# SUPPLY.net
KiCad netlist of a schematic drawn in EAGLE
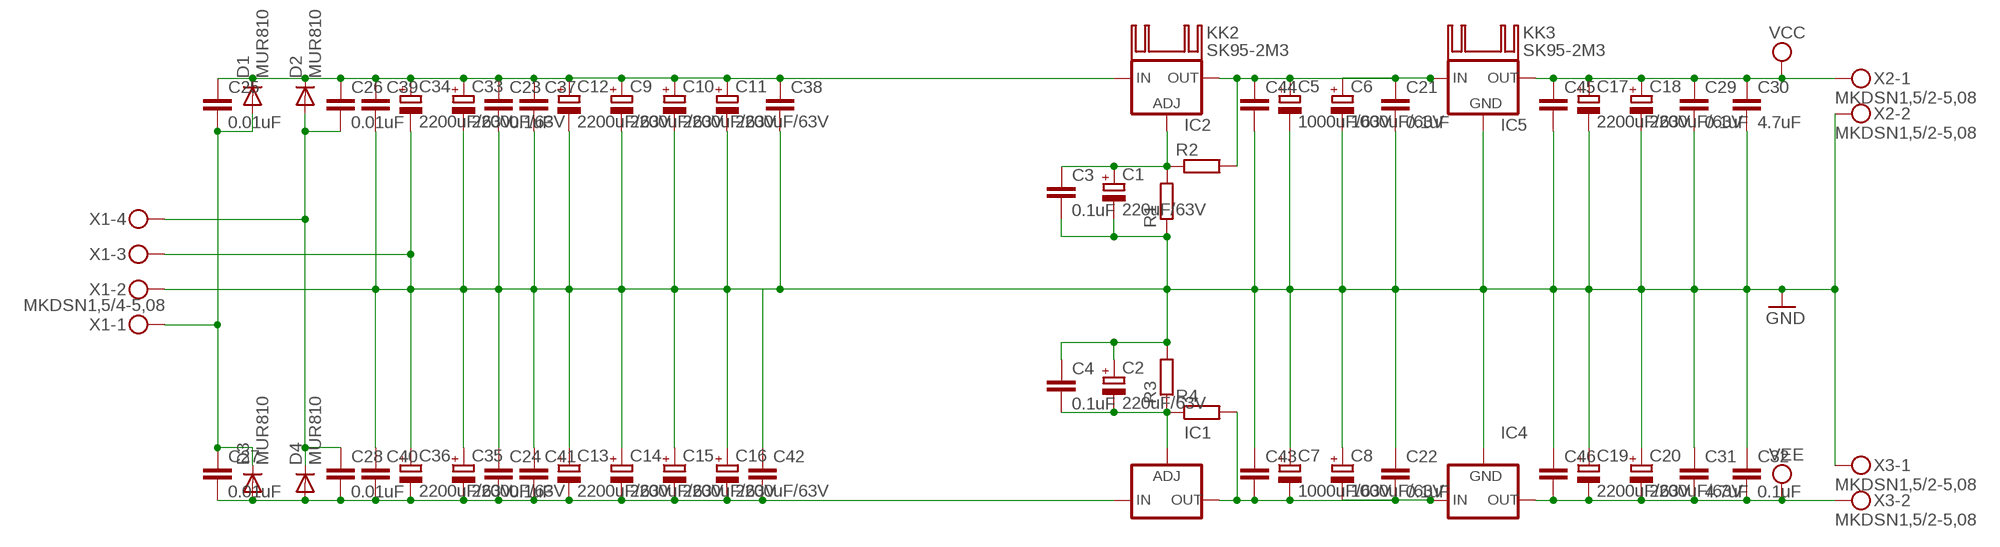
[diagram p0: schematic, sheet 1]

(export (version "E")
  (design (tool "Eeschema 10.0.6"))
  (components
    (comp (ref "C1")
      (value "220uF/63V")
      (footprint "eagle-import:E5-10,5")
      (libsource (lib "eagle-import") (part "CPOL-EUE5-10.5"))
    )
    (comp (ref "C2")
      (value "220uF/63V")
      (footprint "eagle-import:E5-10,5")
      (libsource (lib "eagle-import") (part "CPOL-EUE5-10.5"))
    )
    (comp (ref "C3")
      (value "0.1uF")
      (footprint "eagle-import:C050-035X075")
      (libsource (lib "eagle-import") (part "C-EU050-035X075"))
    )
    (comp (ref "C4")
      (value "0.1uF")
      (footprint "eagle-import:C050-035X075")
      (libsource (lib "eagle-import") (part "C-EU050-035X075"))
    )
    (comp (ref "C5")
      (value "1000uF/63V")
      (footprint "eagle-import:E7,5-16")
      (libsource (lib "eagle-import") (part "CPOL-EUE7.5-16"))
    )
    (comp (ref "C6")
      (value "1000uF/63V")
      (footprint "eagle-import:E7,5-16")
      (libsource (lib "eagle-import") (part "CPOL-EUE7.5-16"))
    )
    (comp (ref "C7")
      (value "1000uF/63V")
      (footprint "eagle-import:E7,5-16")
      (libsource (lib "eagle-import") (part "CPOL-EUE7.5-16"))
    )
    (comp (ref "C8")
      (value "1000uF/63V")
      (footprint "eagle-import:E7,5-16")
      (libsource (lib "eagle-import") (part "CPOL-EUE7.5-16"))
    )
    (comp (ref "C9")
      (value "2200uF/63V")
      (footprint "eagle-import:E7,5-18")
      (libsource (lib "eagle-import") (part "CPOL-EUE7.5-18"))
    )
    (comp (ref "C10")
      (value "2200uF/63V")
      (footprint "eagle-import:E7,5-18")
      (libsource (lib "eagle-import") (part "CPOL-EUE7.5-18"))
    )
    (comp (ref "C11")
      (value "2200uF/63V")
      (footprint "eagle-import:E7,5-18")
      (libsource (lib "eagle-import") (part "CPOL-EUE7.5-18"))
    )
    (comp (ref "C12")
      (value "2200uF/63V")
      (footprint "eagle-import:E7,5-18")
      (libsource (lib "eagle-import") (part "CPOL-EUE7.5-18"))
    )
    (comp (ref "C13")
      (value "2200uF/63V")
      (footprint "eagle-import:E7,5-18")
      (libsource (lib "eagle-import") (part "CPOL-EUE7.5-18"))
    )
    (comp (ref "C14")
      (value "2200uF/63V")
      (footprint "eagle-import:E7,5-18")
      (libsource (lib "eagle-import") (part "CPOL-EUE7.5-18"))
    )
    (comp (ref "C15")
      (value "2200uF/63V")
      (footprint "eagle-import:E7,5-18")
      (libsource (lib "eagle-import") (part "CPOL-EUE7.5-18"))
    )
    (comp (ref "C16")
      (value "2200uF/63V")
      (footprint "eagle-import:E7,5-18")
      (libsource (lib "eagle-import") (part "CPOL-EUE7.5-18"))
    )
    (comp (ref "C17")
      (value "2200uF/63V")
      (footprint "eagle-import:E7,5-18")
      (libsource (lib "eagle-import") (part "CPOL-EUE7.5-18"))
    )
    (comp (ref "C18")
      (value "2200uF/63V")
      (footprint "eagle-import:E7,5-18")
      (libsource (lib "eagle-import") (part "CPOL-EUE7.5-18"))
    )
    (comp (ref "C19")
      (value "2200uF/63V")
      (footprint "eagle-import:E7,5-18")
      (libsource (lib "eagle-import") (part "CPOL-EUE7.5-18"))
    )
    (comp (ref "C20")
      (value "2200uF/63V")
      (footprint "eagle-import:E7,5-18")
      (libsource (lib "eagle-import") (part "CPOL-EUE7.5-18"))
    )
    (comp (ref "C21")
      (value "0.1uF")
      (footprint "eagle-import:C050-035X075")
      (libsource (lib "eagle-import") (part "C-EU050-035X075"))
    )
    (comp (ref "C22")
      (value "0.1uF")
      (footprint "eagle-import:C050-035X075")
      (libsource (lib "eagle-import") (part "C-EU050-035X075"))
    )
    (comp (ref "C23")
      (value "0.1uF")
      (footprint "eagle-import:C050-035X075")
      (libsource (lib "eagle-import") (part "C-EU050-035X075"))
    )
    (comp (ref "C24")
      (value "0.1uF")
      (footprint "eagle-import:C050-035X075")
      (libsource (lib "eagle-import") (part "C-EU050-035X075"))
    )
    (comp (ref "C25")
      (value "0.01uF")
      (footprint "eagle-import:C050-035X075")
      (libsource (lib "eagle-import") (part "C-EU050-035X075"))
    )
    (comp (ref "C26")
      (value "0.01uF")
      (footprint "eagle-import:C050-035X075")
      (libsource (lib "eagle-import") (part "C-EU050-035X075"))
    )
    (comp (ref "C27")
      (value "0.01uF")
      (footprint "eagle-import:C050-035X075")
      (libsource (lib "eagle-import") (part "C-EU050-035X075"))
    )
    (comp (ref "C28")
      (value "0.01uF")
      (footprint "eagle-import:C050-035X075")
      (libsource (lib "eagle-import") (part "C-EU050-035X075"))
    )
    (comp (ref "C29")
      (value "0.1uF")
      (footprint "eagle-import:C102-054X133")
      (libsource (lib "eagle-import") (part "C-EU102-054X133"))
    )
    (comp (ref "C30")
      (value "4.7uF")
      (footprint "eagle-import:C102-054X133")
      (libsource (lib "eagle-import") (part "C-EU102-054X133"))
    )
    (comp (ref "C31")
      (value "4.7uF")
      (footprint "eagle-import:C102-054X133")
      (libsource (lib "eagle-import") (part "C-EU102-054X133"))
    )
    (comp (ref "C32")
      (value "0.1uF")
      (footprint "eagle-import:C102-054X133")
      (libsource (lib "eagle-import") (part "C-EU102-054X133"))
    )
    (comp (ref "C33")
      (value "2200uF/63V")
      (footprint "eagle-import:E7,5-18")
      (libsource (lib "eagle-import") (part "CPOL-EUE7.5-18"))
    )
    (comp (ref "C34")
      (value "2200uF/63V")
      (footprint "eagle-import:E7,5-18")
      (libsource (lib "eagle-import") (part "CPOL-EUE7.5-18"))
    )
    (comp (ref "C35")
      (value "2200uF/63V")
      (footprint "eagle-import:E7,5-18")
      (libsource (lib "eagle-import") (part "CPOL-EUE7.5-18"))
    )
    (comp (ref "C36")
      (value "2200uF/63V")
      (footprint "eagle-import:E7,5-18")
      (libsource (lib "eagle-import") (part "CPOL-EUE7.5-18"))
    )
    (comp (ref "C37")
      (value "C-EUC1210")
      (footprint "eagle-import:C1210")
      (libsource (lib "eagle-import") (part "resistor_C-EUC1210"))
    )
    (comp (ref "C38")
      (value "C-EUC1210")
      (footprint "eagle-import:C1210")
      (libsource (lib "eagle-import") (part "resistor_C-EUC1210"))
    )
    (comp (ref "C39")
      (value "C-EUC1210")
      (footprint "eagle-import:C1210")
      (libsource (lib "eagle-import") (part "resistor_C-EUC1210"))
    )
    (comp (ref "C40")
      (value "C-EUC1210")
      (footprint "eagle-import:C1210")
      (libsource (lib "eagle-import") (part "resistor_C-EUC1210"))
    )
    (comp (ref "C41")
      (value "C-EUC1210")
      (footprint "eagle-import:C1210")
      (libsource (lib "eagle-import") (part "resistor_C-EUC1210"))
    )
    (comp (ref "C42")
      (value "C-EUC1210")
      (footprint "eagle-import:C1210")
      (libsource (lib "eagle-import") (part "resistor_C-EUC1210"))
    )
    (comp (ref "C43")
      (value "C-EUC1210")
      (footprint "eagle-import:C1210")
      (libsource (lib "eagle-import") (part "resistor_C-EUC1210"))
    )
    (comp (ref "C44")
      (value "C-EUC1210")
      (footprint "eagle-import:C1210")
      (libsource (lib "eagle-import") (part "resistor_C-EUC1210"))
    )
    (comp (ref "C45")
      (value "C-EUC1210")
      (footprint "eagle-import:C1210")
      (libsource (lib "eagle-import") (part "resistor_C-EUC1210"))
    )
    (comp (ref "C46")
      (value "C-EUC1210")
      (footprint "eagle-import:C1210")
      (libsource (lib "eagle-import") (part "resistor_C-EUC1210"))
    )
    (comp (ref "D1")
      (value "MUR810")
      (footprint "eagle-import:TO220ACS")
      (libsource (lib "eagle-import") (part "MUR810"))
    )
    (comp (ref "D2")
      (value "MUR810")
      (footprint "eagle-import:TO220ACS")
      (libsource (lib "eagle-import") (part "MUR810"))
    )
    (comp (ref "D3")
      (value "MUR810")
      (footprint "eagle-import:TO220ACS")
      (libsource (lib "eagle-import") (part "MUR810"))
    )
    (comp (ref "D4")
      (value "MUR810")
      (footprint "eagle-import:TO220ACS")
      (libsource (lib "eagle-import") (part "MUR810"))
    )
    (comp (ref "IC1")
      (value "LM337TS")
      (footprint "eagle-import:337TS")
      (libsource (lib "eagle-import") (part "LM337TS"))
    )
    (comp (ref "IC2")
      (value "LM317TS")
      (footprint "eagle-import:317TS")
      (libsource (lib "eagle-import") (part "LM317TS"))
    )
    (comp (ref "IC4")
      (value "79XXS")
      (footprint "eagle-import:79XXS")
      (libsource (lib "eagle-import") (part "79XXS"))
    )
    (comp (ref "IC5")
      (value "78XXS")
      (footprint "eagle-import:78XXS")
      (libsource (lib "eagle-import") (part "78XXS"))
    )
    (comp (ref "KK2")
      (value "SK95-2M3")
      (footprint "eagle-import:SK95-2M3")
      (libsource (lib "eagle-import") (part "SK95-2M3"))
    )
    (comp (ref "KK3")
      (value "SK95-2M3")
      (footprint "eagle-import:SK95-2M3")
      (libsource (lib "eagle-import") (part "SK95-2M3"))
    )
    (comp (ref "R1")
      (value "R-EU_0207/10")
      (footprint "eagle-import:0207_10")
      (libsource (lib "eagle-import") (part "R-EU_0207/10"))
    )
    (comp (ref "R2")
      (value "R-EU_0207/10")
      (footprint "eagle-import:0207_10")
      (libsource (lib "eagle-import") (part "R-EU_0207/10"))
    )
    (comp (ref "R3")
      (value "R-EU_0207/10")
      (footprint "eagle-import:0207_10")
      (libsource (lib "eagle-import") (part "R-EU_0207/10"))
    )
    (comp (ref "R4")
      (value "R-EU_0207/10")
      (footprint "eagle-import:0207_10")
      (libsource (lib "eagle-import") (part "R-EU_0207/10"))
    )
    (comp (ref "X1")
      (value "MKDSN1,5/4-5,08")
      (footprint "eagle-import:MKDSN1,5_4-5,08")
      (libsource (lib "eagle-import") (part "MKDSN1,5/4-5,08"))
    )
    (comp (ref "X2")
      (value "MKDSN1,5/2-5,08")
      (footprint "eagle-import:MKDSN1,5_2-5,08")
      (libsource (lib "eagle-import") (part "MKDSN1,5/2-5,08"))
    )
    (comp (ref "X3")
      (value "MKDSN1,5/2-5,08")
      (footprint "eagle-import:MKDSN1,5_2-5,08")
      (libsource (lib "eagle-import") (part "MKDSN1,5/2-5,08"))
    )
  )
  (nets
    (net (code "1") (name "GND") (class "Default")
      (node (ref "C1") (pin "-") (pinfunction "-_-") (pintype "passive"))
      (node (ref "C10") (pin "-") (pinfunction "-_-") (pintype "passive"))
      (node (ref "C11") (pin "-") (pinfunction "-_-") (pintype "passive"))
      (node (ref "C12") (pin "-") (pinfunction "-_-") (pintype "passive"))
      (node (ref "C13") (pin "+") (pinfunction "+_+") (pintype "passive"))
      (node (ref "C14") (pin "+") (pinfunction "+_+") (pintype "passive"))
      (node (ref "C15") (pin "+") (pinfunction "+_+") (pintype "passive"))
      (node (ref "C16") (pin "+") (pinfunction "+_+") (pintype "passive"))
      (node (ref "C17") (pin "-") (pinfunction "-_-") (pintype "passive"))
      (node (ref "C18") (pin "-") (pinfunction "-_-") (pintype "passive"))
      (node (ref "C19") (pin "+") (pinfunction "+_+") (pintype "passive"))
      (node (ref "C2") (pin "+") (pinfunction "+_+") (pintype "passive"))
      (node (ref "C20") (pin "+") (pinfunction "+_+") (pintype "passive"))
      (node (ref "C21") (pin "2") (pinfunction "2_2") (pintype "passive"))
      (node (ref "C22") (pin "1") (pinfunction "1_1") (pintype "passive"))
      (node (ref "C23") (pin "2") (pinfunction "2_2") (pintype "passive"))
      (node (ref "C24") (pin "1") (pinfunction "1_1") (pintype "passive"))
      (node (ref "C29") (pin "2") (pinfunction "2_2") (pintype "passive"))
      (node (ref "C3") (pin "2") (pinfunction "2_2") (pintype "passive"))
      (node (ref "C30") (pin "2") (pinfunction "2_2") (pintype "passive"))
      (node (ref "C31") (pin "1") (pinfunction "1_1") (pintype "passive"))
      (node (ref "C32") (pin "1") (pinfunction "1_1") (pintype "passive"))
      (node (ref "C33") (pin "-") (pinfunction "-_-") (pintype "passive"))
      (node (ref "C34") (pin "-") (pinfunction "-_-") (pintype "passive"))
      (node (ref "C35") (pin "+") (pinfunction "+_+") (pintype "passive"))
      (node (ref "C36") (pin "+") (pinfunction "+_+") (pintype "passive"))
      (node (ref "C37") (pin "2") (pinfunction "2_2") (pintype "passive"))
      (node (ref "C38") (pin "2") (pinfunction "2_2") (pintype "passive"))
      (node (ref "C39") (pin "2") (pinfunction "2_2") (pintype "passive"))
      (node (ref "C4") (pin "1") (pinfunction "1_1") (pintype "passive"))
      (node (ref "C40") (pin "1") (pinfunction "1_1") (pintype "passive"))
      (node (ref "C41") (pin "1") (pinfunction "1_1") (pintype "passive"))
      (node (ref "C42") (pin "1") (pinfunction "1_1") (pintype "passive"))
      (node (ref "C43") (pin "1") (pinfunction "1_1") (pintype "passive"))
      (node (ref "C44") (pin "2") (pinfunction "2_2") (pintype "passive"))
      (node (ref "C45") (pin "2") (pinfunction "2_2") (pintype "passive"))
      (node (ref "C46") (pin "1") (pinfunction "1_1") (pintype "passive"))
      (node (ref "C5") (pin "-") (pinfunction "-_-") (pintype "passive"))
      (node (ref "C6") (pin "-") (pinfunction "-_-") (pintype "passive"))
      (node (ref "C7") (pin "+") (pinfunction "+_+") (pintype "passive"))
      (node (ref "C8") (pin "+") (pinfunction "+_+") (pintype "passive"))
      (node (ref "C9") (pin "-") (pinfunction "-_-") (pintype "passive"))
      (node (ref "IC4") (pin "GND") (pinfunction "GND_GND") (pintype "input"))
      (node (ref "IC5") (pin "GND") (pinfunction "GND_GND") (pintype "input"))
      (node (ref "R1") (pin "1") (pinfunction "1_1") (pintype "passive"))
      (node (ref "R3") (pin "2") (pinfunction "2_2") (pintype "passive"))
      (node (ref "X1") (pin "2") (pinfunction "KL_2") (pintype "passive"))
      (node (ref "X1") (pin "3") (pinfunction "KL_3") (pintype "passive"))
      (node (ref "X2") (pin "2") (pinfunction "KL_2") (pintype "passive"))
      (node (ref "X3") (pin "1") (pinfunction "KL_1") (pintype "passive"))
    )
    (net (code "2") (name "Net-(IC1-ADJ)") (class "Default")
      (node (ref "C2") (pin "-") (pinfunction "-_-") (pintype "passive"))
      (node (ref "C4") (pin "2") (pinfunction "2_2") (pintype "passive"))
      (node (ref "IC1") (pin "1") (pinfunction "ADJ_1") (pintype "input"))
      (node (ref "R3") (pin "1") (pinfunction "1_1") (pintype "passive"))
      (node (ref "R4") (pin "1") (pinfunction "1_1") (pintype "passive"))
    )
    (net (code "3") (name "Net-(IC1-IN)") (class "Default")
      (node (ref "C13") (pin "-") (pinfunction "-_-") (pintype "passive"))
      (node (ref "C14") (pin "-") (pinfunction "-_-") (pintype "passive"))
      (node (ref "C15") (pin "-") (pinfunction "-_-") (pintype "passive"))
      (node (ref "C16") (pin "-") (pinfunction "-_-") (pintype "passive"))
      (node (ref "C24") (pin "2") (pinfunction "2_2") (pintype "passive"))
      (node (ref "C27") (pin "2") (pinfunction "2_2") (pintype "passive"))
      (node (ref "C28") (pin "2") (pinfunction "2_2") (pintype "passive"))
      (node (ref "C35") (pin "-") (pinfunction "-_-") (pintype "passive"))
      (node (ref "C36") (pin "-") (pinfunction "-_-") (pintype "passive"))
      (node (ref "C40") (pin "2") (pinfunction "2_2") (pintype "passive"))
      (node (ref "C41") (pin "2") (pinfunction "2_2") (pintype "passive"))
      (node (ref "C42") (pin "2") (pinfunction "2_2") (pintype "passive"))
      (node (ref "D3") (pin "A") (pinfunction "A_A") (pintype "passive"))
      (node (ref "D4") (pin "A") (pinfunction "A_A") (pintype "passive"))
      (node (ref "IC1") (pin "2") (pinfunction "IN_2") (pintype "input"))
    )
    (net (code "4") (name "Net-(IC1-OUT)") (class "Default")
      (node (ref "C22") (pin "2") (pinfunction "2_2") (pintype "passive"))
      (node (ref "C43") (pin "2") (pinfunction "2_2") (pintype "passive"))
      (node (ref "C7") (pin "-") (pinfunction "-_-") (pintype "passive"))
      (node (ref "C8") (pin "-") (pinfunction "-_-") (pintype "passive"))
      (node (ref "IC1") (pin "3") (pinfunction "OUT_3") (pintype "passive"))
      (node (ref "IC4") (pin "IN") (pinfunction "IN_IN") (pintype "input"))
      (node (ref "R4") (pin "2") (pinfunction "2_2") (pintype "passive"))
    )
    (net (code "5") (name "Net-(IC2-ADJ)") (class "Default")
      (node (ref "C1") (pin "+") (pinfunction "+_+") (pintype "passive"))
      (node (ref "C3") (pin "1") (pinfunction "1_1") (pintype "passive"))
      (node (ref "IC2") (pin "1") (pinfunction "ADJ_1") (pintype "input"))
      (node (ref "R1") (pin "2") (pinfunction "2_2") (pintype "passive"))
      (node (ref "R2") (pin "1") (pinfunction "1_1") (pintype "passive"))
    )
    (net (code "6") (name "Net-(IC2-IN)") (class "Default")
      (node (ref "C10") (pin "+") (pinfunction "+_+") (pintype "passive"))
      (node (ref "C11") (pin "+") (pinfunction "+_+") (pintype "passive"))
      (node (ref "C12") (pin "+") (pinfunction "+_+") (pintype "passive"))
      (node (ref "C23") (pin "1") (pinfunction "1_1") (pintype "passive"))
      (node (ref "C25") (pin "1") (pinfunction "1_1") (pintype "passive"))
      (node (ref "C26") (pin "1") (pinfunction "1_1") (pintype "passive"))
      (node (ref "C33") (pin "+") (pinfunction "+_+") (pintype "passive"))
      (node (ref "C34") (pin "+") (pinfunction "+_+") (pintype "passive"))
      (node (ref "C37") (pin "1") (pinfunction "1_1") (pintype "passive"))
      (node (ref "C38") (pin "1") (pinfunction "1_1") (pintype "passive"))
      (node (ref "C39") (pin "1") (pinfunction "1_1") (pintype "passive"))
      (node (ref "C9") (pin "+") (pinfunction "+_+") (pintype "passive"))
      (node (ref "D1") (pin "C") (pinfunction "C_C") (pintype "passive"))
      (node (ref "D2") (pin "C") (pinfunction "C_C") (pintype "passive"))
      (node (ref "IC2") (pin "3") (pinfunction "IN_3") (pintype "input"))
    )
    (net (code "7") (name "Net-(IC2-OUT)") (class "Default")
      (node (ref "C21") (pin "1") (pinfunction "1_1") (pintype "passive"))
      (node (ref "C44") (pin "1") (pinfunction "1_1") (pintype "passive"))
      (node (ref "C5") (pin "+") (pinfunction "+_+") (pintype "passive"))
      (node (ref "C6") (pin "+") (pinfunction "+_+") (pintype "passive"))
      (node (ref "IC2") (pin "2") (pinfunction "OUT_2") (pintype "passive"))
      (node (ref "IC5") (pin "IN") (pinfunction "IN_IN") (pintype "input"))
      (node (ref "R2") (pin "2") (pinfunction "2_2") (pintype "passive"))
    )
    (net (code "8") (name "Net-(X1A-KL)") (class "Default")
      (node (ref "C25") (pin "2") (pinfunction "2_2") (pintype "passive"))
      (node (ref "C27") (pin "1") (pinfunction "1_1") (pintype "passive"))
      (node (ref "D1") (pin "A") (pinfunction "A_A") (pintype "passive"))
      (node (ref "D3") (pin "C") (pinfunction "C_C") (pintype "passive"))
      (node (ref "X1") (pin "1") (pinfunction "KL_1") (pintype "passive"))
    )
    (net (code "9") (name "Net-(X1D-KL)") (class "Default")
      (node (ref "C26") (pin "2") (pinfunction "2_2") (pintype "passive"))
      (node (ref "C28") (pin "1") (pinfunction "1_1") (pintype "passive"))
      (node (ref "D2") (pin "A") (pinfunction "A_A") (pintype "passive"))
      (node (ref "D4") (pin "C") (pinfunction "C_C") (pintype "passive"))
      (node (ref "X1") (pin "4") (pinfunction "KL_4") (pintype "passive"))
    )
    (net (code "10") (name "VCC") (class "Default")
      (node (ref "C17") (pin "+") (pinfunction "+_+") (pintype "passive"))
      (node (ref "C18") (pin "+") (pinfunction "+_+") (pintype "passive"))
      (node (ref "C29") (pin "1") (pinfunction "1_1") (pintype "passive"))
      (node (ref "C30") (pin "1") (pinfunction "1_1") (pintype "passive"))
      (node (ref "C45") (pin "1") (pinfunction "1_1") (pintype "passive"))
      (node (ref "IC5") (pin "OUT") (pinfunction "OUT_OUT") (pintype "passive"))
      (node (ref "X2") (pin "1") (pinfunction "KL_1") (pintype "passive"))
    )
    (net (code "11") (name "VEE") (class "Default")
      (node (ref "C19") (pin "-") (pinfunction "-_-") (pintype "passive"))
      (node (ref "C20") (pin "-") (pinfunction "-_-") (pintype "passive"))
      (node (ref "C31") (pin "2") (pinfunction "2_2") (pintype "passive"))
      (node (ref "C32") (pin "2") (pinfunction "2_2") (pintype "passive"))
      (node (ref "C46") (pin "2") (pinfunction "2_2") (pintype "passive"))
      (node (ref "IC4") (pin "OUT") (pinfunction "OUT_OUT") (pintype "passive"))
      (node (ref "X3") (pin "2") (pinfunction "KL_2") (pintype "passive"))
    )
  )
)
